# WHRL.net
KiCad netlist of a schematic drawn in EAGLE
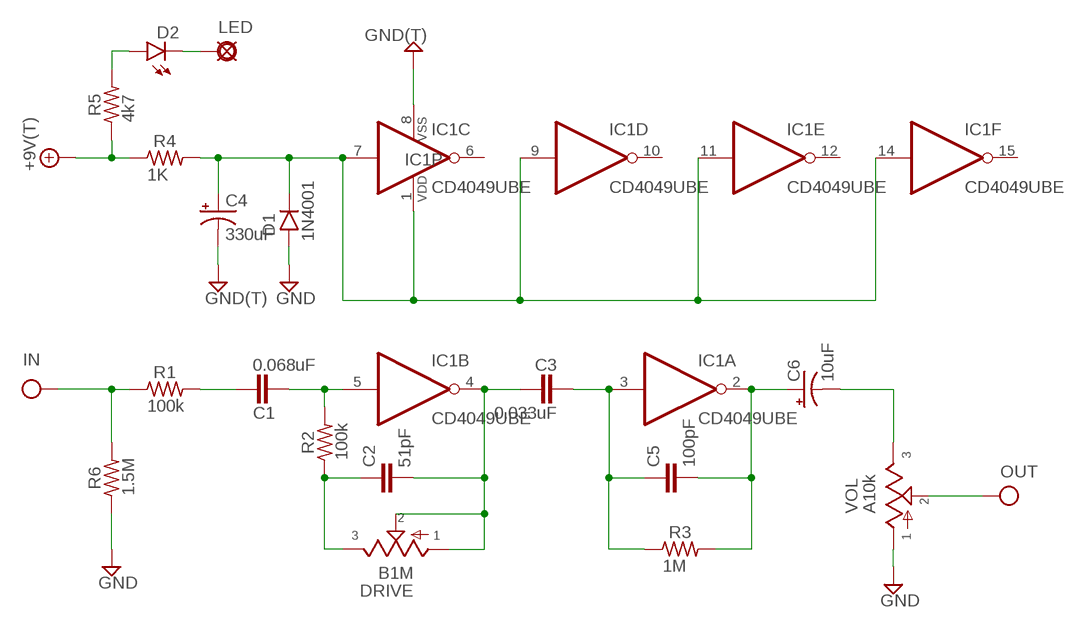
[diagram p0: schematic, sheet 1]

(export (version "E")
  (design (tool "Eeschema 10.0.6"))
  (components
    (comp (ref "+9V")
      (value "+9V(T)")
      (footprint "eagle-import:SQUARE")
      (libsource (lib "eagle-import") (part "+9V(T)"))
    )
    (comp (ref "C1")
      (value "0.068uF")
      (footprint "eagle-import:072X035")
      (libsource (lib "eagle-import") (part "072X0352"))
    )
    (comp (ref "C2")
      (value "51pF")
      (footprint "eagle-import:050X030_025")
      (libsource (lib "eagle-import") (part "050X030_0251"))
    )
    (comp (ref "C3")
      (value "0.033uF")
      (footprint "eagle-import:072X025")
      (libsource (lib "eagle-import") (part "072X0252"))
    )
    (comp (ref "C4")
      (value "330uF")
      (footprint "eagle-import:080_035_1")
      (libsource (lib "eagle-import") (part "0801"))
    )
    (comp (ref "C5")
      (value "100pF")
      (footprint "eagle-import:050X030_025")
      (libsource (lib "eagle-import") (part "050X030_0251"))
    )
    (comp (ref "C6")
      (value "10uF")
      (footprint "eagle-import:050_020_1")
      (libsource (lib "eagle-import") (part "0501"))
    )
    (comp (ref "D1")
      (value "1N4001")
      (footprint "eagle-import:DO41-2")
      (libsource (lib "eagle-import") (part "1N400X.2"))
    )
    (comp (ref "D2")
      (value "LED3MM")
      (footprint "eagle-import:LED3MM")
      (libsource (lib "eagle-import") (part "LED3MM"))
    )
    (comp (ref "DRIVE")
      (value "B1M")
      (footprint "eagle-import:POT_9MM_HOLES")
      (libsource (lib "eagle-import") (part "9MMPOT_9MM_HOLES"))
    )
    (comp (ref "G")
      (value "GND(T)")
      (footprint "eagle-import:SQUARE")
      (libsource (lib "eagle-import") (part "GND(T)"))
    )
    (comp (ref "G2")
      (value "GND(T)")
      (footprint "eagle-import:SQUARE")
      (libsource (lib "eagle-import") (part "GND(T)"))
    )
    (comp (ref "IC1")
      (value "CD4049UBE")
      (footprint "eagle-import:DIL16")
      (libsource (lib "eagle-import") (part "CD4049UBE"))
    )
    (comp (ref "IN")
      (value "IN(T)")
      (footprint "eagle-import:SQUARE")
      (libsource (lib "eagle-import") (part "IN(T)"))
    )
    (comp (ref "LED")
      (value "PAD")
      (footprint "eagle-import:SQUARE")
      (libsource (lib "eagle-import") (part "PAD"))
    )
    (comp (ref "OUT")
      (value "OUT(T)")
      (footprint "eagle-import:SQUARE")
      (libsource (lib "eagle-import") (part "OUT(T)"))
    )
    (comp (ref "R1")
      (value "100k")
      (footprint "eagle-import:R0204_2")
      (libsource (lib "eagle-import") (part "3MM.2"))
    )
    (comp (ref "R2")
      (value "100k")
      (footprint "eagle-import:R0204_2")
      (libsource (lib "eagle-import") (part "3MM.2"))
    )
    (comp (ref "R3")
      (value "1M")
      (footprint "eagle-import:R0204_2")
      (libsource (lib "eagle-import") (part "3MM.2"))
    )
    (comp (ref "R4")
      (value "1K")
      (footprint "eagle-import:R0204_2")
      (libsource (lib "eagle-import") (part "3MM.2"))
    )
    (comp (ref "R5")
      (value "4k7")
      (footprint "eagle-import:R0204_2")
      (libsource (lib "eagle-import") (part "3MM.2"))
    )
    (comp (ref "R6")
      (value "1.5M")
      (footprint "eagle-import:R0204_2")
      (libsource (lib "eagle-import") (part "3MM.2"))
    )
    (comp (ref "VOL")
      (value "A10k")
      (footprint "eagle-import:POT_9MM_HOLES")
      (libsource (lib "eagle-import") (part "9MMPOT_9MM_HOLES"))
    )
  )
  (nets
    (net (code "1") (name "+9V(T)") (class "Default")
      (node (ref "+9V") (pin "1") (pinfunction "+9V_1") (pintype "power_in"))
      (node (ref "R4") (pin "1") (pinfunction "1_1") (pintype "passive"))
      (node (ref "R5") (pin "1") (pinfunction "1_1") (pintype "passive"))
    )
    (net (code "2") (name "GND") (class "Default")
      (node (ref "C4") (pin "-") (pinfunction "-_-") (pintype "passive"))
      (node (ref "D1") (pin "A") (pinfunction "A_A") (pintype "passive"))
      (node (ref "G") (pin "1") (pinfunction "GND_1") (pintype "power_in"))
      (node (ref "G2") (pin "1") (pinfunction "GND_1") (pintype "power_in"))
      (node (ref "IC1") (pin "8") (pinfunction "VSS_8") (pintype "power_in"))
      (node (ref "R6") (pin "1") (pinfunction "1_1") (pintype "passive"))
      (node (ref "VOL") (pin "P$1") (pinfunction "P$1_P$1") (pintype "bidirectional"))
    )
    (net (code "3") (name "IN(T)") (class "Default")
      (node (ref "IN") (pin "1") (pinfunction "IN_1") (pintype "power_in"))
      (node (ref "R1") (pin "1") (pinfunction "1_1") (pintype "passive"))
      (node (ref "R6") (pin "2") (pinfunction "2_2") (pintype "passive"))
    )
    (net (code "4") (name "Net-(C1-Pad2)") (class "Default")
      (node (ref "C1") (pin "2") (pinfunction "2_2") (pintype "passive"))
      (node (ref "R1") (pin "2") (pinfunction "2_2") (pintype "passive"))
    )
    (net (code "5") (name "Net-(C2-Pad1)") (class "Default")
      (node (ref "C2") (pin "1") (pinfunction "1_1") (pintype "passive"))
      (node (ref "DRIVE") (pin "P$3") (pinfunction "P$3_P$3") (pintype "bidirectional"))
      (node (ref "R2") (pin "1") (pinfunction "1_1") (pintype "passive"))
    )
    (net (code "6") (name "Net-(C6-Pad-)") (class "Default")
      (node (ref "C6") (pin "-") (pinfunction "-_-") (pintype "passive"))
      (node (ref "VOL") (pin "P$3") (pinfunction "P$3_P$3") (pintype "bidirectional"))
    )
    (net (code "7") (name "Net-(D2-C)") (class "Default")
      (node (ref "D2") (pin "K") (pinfunction "C_K") (pintype "passive"))
      (node (ref "LED") (pin "1") (pinfunction "PAD_1") (pintype "passive"))
    )
    (net (code "8") (name "Net-(D2-PadA)") (class "Default")
      (node (ref "D2") (pin "A") (pinfunction "A_A") (pintype "passive"))
      (node (ref "R5") (pin "2") (pinfunction "2_2") (pintype "passive"))
    )
    (net (code "9") (name "Net-(IC1A-I)") (class "Default")
      (node (ref "C3") (pin "2") (pinfunction "2_2") (pintype "passive"))
      (node (ref "C5") (pin "1") (pinfunction "1_1") (pintype "passive"))
      (node (ref "IC1") (pin "3") (pinfunction "I_3") (pintype "input"))
      (node (ref "R3") (pin "1") (pinfunction "1_1") (pintype "passive"))
    )
    (net (code "10") (name "Net-(IC1A-O)") (class "Default")
      (node (ref "C5") (pin "2") (pinfunction "2_2") (pintype "passive"))
      (node (ref "C6") (pin "+") (pinfunction "+_+") (pintype "passive"))
      (node (ref "IC1") (pin "2") (pinfunction "O_2") (pintype "output"))
      (node (ref "R3") (pin "2") (pinfunction "2_2") (pintype "passive"))
    )
    (net (code "11") (name "Net-(IC1B-I)") (class "Default")
      (node (ref "C1") (pin "1") (pinfunction "1_1") (pintype "passive"))
      (node (ref "IC1") (pin "5") (pinfunction "I_5") (pintype "input"))
      (node (ref "R2") (pin "2") (pinfunction "2_2") (pintype "passive"))
    )
    (net (code "12") (name "Net-(IC1B-O)") (class "Default")
      (node (ref "C2") (pin "2") (pinfunction "2_2") (pintype "passive"))
      (node (ref "C3") (pin "1") (pinfunction "1_1") (pintype "passive"))
      (node (ref "DRIVE") (pin "P$1") (pinfunction "P$1_P$1") (pintype "bidirectional"))
      (node (ref "DRIVE") (pin "P$2") (pinfunction "P$2_P$2") (pintype "bidirectional"))
      (node (ref "IC1") (pin "4") (pinfunction "O_4") (pintype "output"))
    )
    (net (code "13") (name "Net-(IC1C-I)") (class "Default")
      (node (ref "C4") (pin "+") (pinfunction "+_+") (pintype "passive"))
      (node (ref "D1") (pin "C") (pinfunction "C_C") (pintype "passive"))
      (node (ref "IC1") (pin "1") (pinfunction "VDD_1") (pintype "power_in"))
      (node (ref "IC1") (pin "11") (pinfunction "I_11") (pintype "input"))
      (node (ref "IC1") (pin "14") (pinfunction "I_14") (pintype "input"))
      (node (ref "IC1") (pin "7") (pinfunction "I_7") (pintype "input"))
      (node (ref "IC1") (pin "9") (pinfunction "I_9") (pintype "input"))
      (node (ref "R4") (pin "2") (pinfunction "2_2") (pintype "passive"))
    )
    (net (code "14") (name "OUT(T)") (class "Default")
      (node (ref "OUT") (pin "1") (pinfunction "OUT_1") (pintype "power_in"))
      (node (ref "VOL") (pin "P$2") (pinfunction "P$2_P$2") (pintype "bidirectional"))
    )
    (net (code "15") (name "unconnected-(IC1C-O-Pad6)") (class "Default")
      (node (ref "IC1") (pin "6") (pinfunction "O_6") (pintype "output"))
    )
    (net (code "16") (name "unconnected-(IC1D-O-Pad10)") (class "Default")
      (node (ref "IC1") (pin "10") (pinfunction "O_10") (pintype "output"))
    )
    (net (code "17") (name "unconnected-(IC1E-O-Pad12)") (class "Default")
      (node (ref "IC1") (pin "12") (pinfunction "O_12") (pintype "output"))
    )
    (net (code "18") (name "unconnected-(IC1F-O-Pad15)") (class "Default")
      (node (ref "IC1") (pin "15") (pinfunction "O_15") (pintype "output"))
    )
  )
)
